# resistance_measuring_board.net
KiCad netlist of a schematic drawn in EAGLE
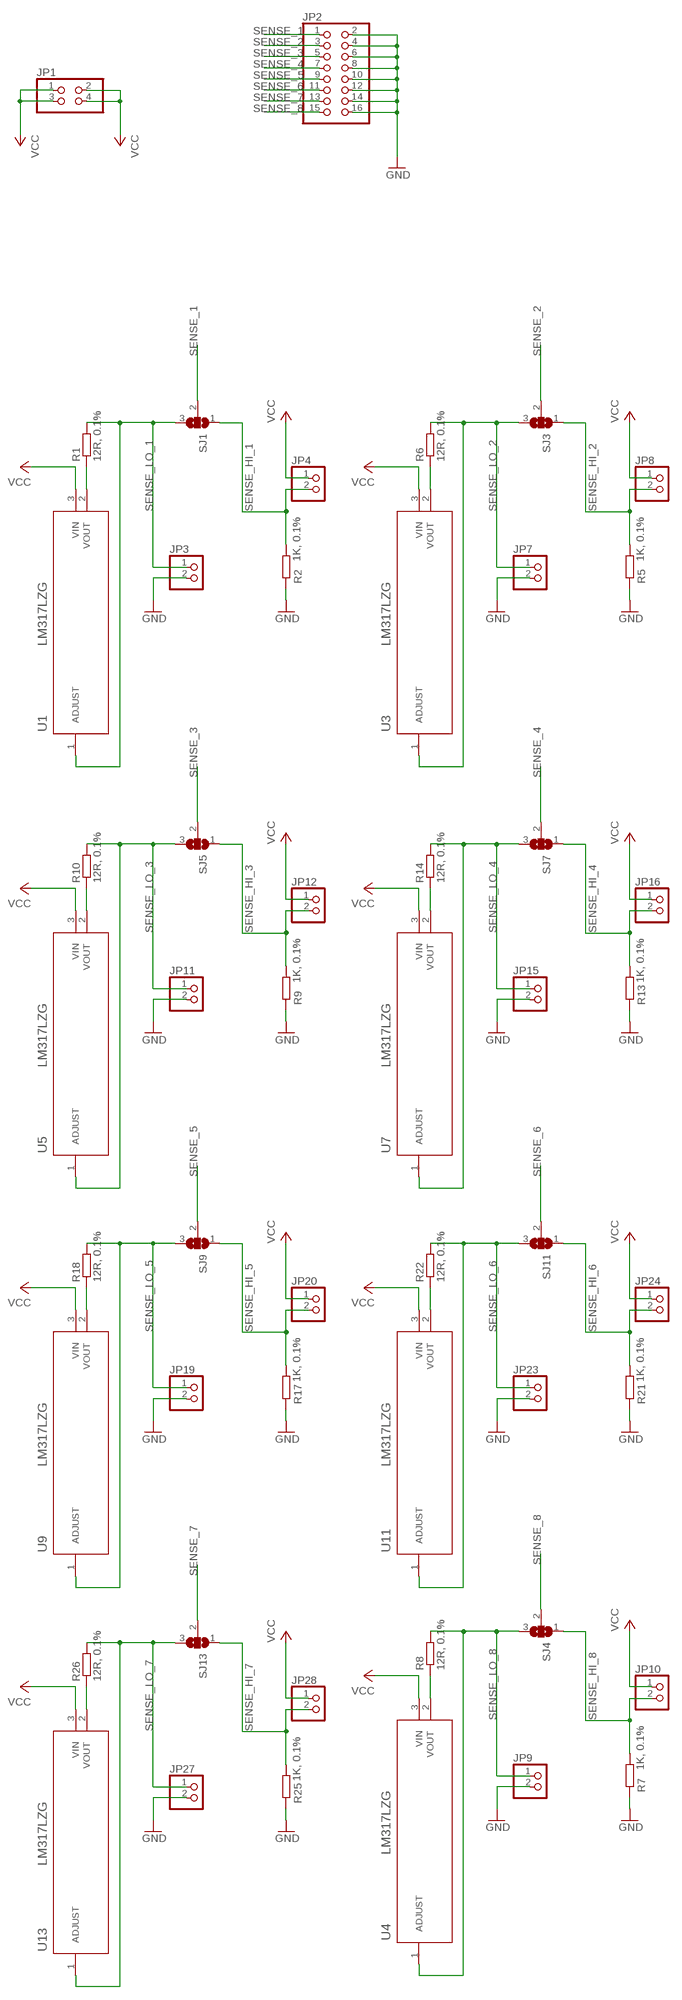
[diagram p0: schematic, sheet 1]

(export (version "E")
  (design (tool "Eeschema 10.0.6"))
  (components
    (comp (ref "JP1")
      (value "PINHD-2X2/90")
      (footprint "eagle-import:2X02_90")
      (libsource (lib "eagle-import") (part "PINHD-2X2/90"))
    )
    (comp (ref "JP2")
      (value "PINHD-2X8/90")
      (footprint "eagle-import:2X08_90")
      (libsource (lib "eagle-import") (part "PINHD-2X8/90"))
    )
    (comp (ref "JP3")
      (value "PINHD-1X2")
      (footprint "eagle-import:1X02")
      (libsource (lib "eagle-import") (part "PINHD-1X2"))
    )
    (comp (ref "JP4")
      (value "PINHD-1X2")
      (footprint "eagle-import:1X02")
      (libsource (lib "eagle-import") (part "PINHD-1X2"))
    )
    (comp (ref "JP7")
      (value "PINHD-1X2")
      (footprint "eagle-import:1X02")
      (libsource (lib "eagle-import") (part "PINHD-1X2"))
    )
    (comp (ref "JP8")
      (value "PINHD-1X2")
      (footprint "eagle-import:1X02")
      (libsource (lib "eagle-import") (part "PINHD-1X2"))
    )
    (comp (ref "JP9")
      (value "PINHD-1X2")
      (footprint "eagle-import:1X02")
      (libsource (lib "eagle-import") (part "PINHD-1X2"))
    )
    (comp (ref "JP10")
      (value "PINHD-1X2")
      (footprint "eagle-import:1X02")
      (libsource (lib "eagle-import") (part "PINHD-1X2"))
    )
    (comp (ref "JP11")
      (value "PINHD-1X2")
      (footprint "eagle-import:1X02")
      (libsource (lib "eagle-import") (part "PINHD-1X2"))
    )
    (comp (ref "JP12")
      (value "PINHD-1X2")
      (footprint "eagle-import:1X02")
      (libsource (lib "eagle-import") (part "PINHD-1X2"))
    )
    (comp (ref "JP15")
      (value "PINHD-1X2")
      (footprint "eagle-import:1X02")
      (libsource (lib "eagle-import") (part "PINHD-1X2"))
    )
    (comp (ref "JP16")
      (value "PINHD-1X2")
      (footprint "eagle-import:1X02")
      (libsource (lib "eagle-import") (part "PINHD-1X2"))
    )
    (comp (ref "JP19")
      (value "PINHD-1X2")
      (footprint "eagle-import:1X02")
      (libsource (lib "eagle-import") (part "PINHD-1X2"))
    )
    (comp (ref "JP20")
      (value "PINHD-1X2")
      (footprint "eagle-import:1X02")
      (libsource (lib "eagle-import") (part "PINHD-1X2"))
    )
    (comp (ref "JP23")
      (value "PINHD-1X2")
      (footprint "eagle-import:1X02")
      (libsource (lib "eagle-import") (part "PINHD-1X2"))
    )
    (comp (ref "JP24")
      (value "PINHD-1X2")
      (footprint "eagle-import:1X02")
      (libsource (lib "eagle-import") (part "PINHD-1X2"))
    )
    (comp (ref "JP27")
      (value "PINHD-1X2")
      (footprint "eagle-import:1X02")
      (libsource (lib "eagle-import") (part "PINHD-1X2"))
    )
    (comp (ref "JP28")
      (value "PINHD-1X2")
      (footprint "eagle-import:1X02")
      (libsource (lib "eagle-import") (part "PINHD-1X2"))
    )
    (comp (ref "R1")
      (value "12R, 0.1%")
      (footprint "eagle-import:R0603")
      (libsource (lib "eagle-import") (part "R-EU_R0603"))
    )
    (comp (ref "R2")
      (value "1K, 0.1%")
      (footprint "eagle-import:R1206")
      (libsource (lib "eagle-import") (part "R-EU_R1206"))
    )
    (comp (ref "R5")
      (value "1K, 0.1%")
      (footprint "eagle-import:R1206")
      (libsource (lib "eagle-import") (part "R-EU_R1206"))
    )
    (comp (ref "R6")
      (value "12R, 0.1%")
      (footprint "eagle-import:R0603")
      (libsource (lib "eagle-import") (part "R-EU_R0603"))
    )
    (comp (ref "R7")
      (value "1K, 0.1%")
      (footprint "eagle-import:R1206")
      (libsource (lib "eagle-import") (part "R-EU_R1206"))
    )
    (comp (ref "R8")
      (value "12R, 0.1%")
      (footprint "eagle-import:R0603")
      (libsource (lib "eagle-import") (part "R-EU_R0603"))
    )
    (comp (ref "R9")
      (value "1K, 0.1%")
      (footprint "eagle-import:R1206")
      (libsource (lib "eagle-import") (part "R-EU_R1206"))
    )
    (comp (ref "R10")
      (value "12R, 0.1%")
      (footprint "eagle-import:R0603")
      (libsource (lib "eagle-import") (part "R-EU_R0603"))
    )
    (comp (ref "R13")
      (value "1K, 0.1%")
      (footprint "eagle-import:R1206")
      (libsource (lib "eagle-import") (part "R-EU_R1206"))
    )
    (comp (ref "R14")
      (value "12R, 0.1%")
      (footprint "eagle-import:R0603")
      (libsource (lib "eagle-import") (part "R-EU_R0603"))
    )
    (comp (ref "R17")
      (value "1K, 0.1%")
      (footprint "eagle-import:R1206")
      (libsource (lib "eagle-import") (part "R-EU_R1206"))
    )
    (comp (ref "R18")
      (value "12R, 0.1%")
      (footprint "eagle-import:R0603")
      (libsource (lib "eagle-import") (part "R-EU_R0603"))
    )
    (comp (ref "R21")
      (value "1K, 0.1%")
      (footprint "eagle-import:R1206")
      (libsource (lib "eagle-import") (part "R-EU_R1206"))
    )
    (comp (ref "R22")
      (value "12R, 0.1%")
      (footprint "eagle-import:R0603")
      (libsource (lib "eagle-import") (part "R-EU_R0603"))
    )
    (comp (ref "R25")
      (value "1K, 0.1%")
      (footprint "eagle-import:R1206")
      (libsource (lib "eagle-import") (part "R-EU_R1206"))
    )
    (comp (ref "R26")
      (value "12R, 0.1%")
      (footprint "eagle-import:R0603")
      (libsource (lib "eagle-import") (part "R-EU_R0603"))
    )
    (comp (ref "SJ1")
      (value "SJ2W")
      (footprint "eagle-import:SJ_2")
      (libsource (lib "eagle-import") (part "SJ2W"))
    )
    (comp (ref "SJ3")
      (value "SJ2W")
      (footprint "eagle-import:SJ_2")
      (libsource (lib "eagle-import") (part "SJ2W"))
    )
    (comp (ref "SJ4")
      (value "SJ2W")
      (footprint "eagle-import:SJ_2")
      (libsource (lib "eagle-import") (part "SJ2W"))
    )
    (comp (ref "SJ5")
      (value "SJ2W")
      (footprint "eagle-import:SJ_2")
      (libsource (lib "eagle-import") (part "SJ2W"))
    )
    (comp (ref "SJ7")
      (value "SJ2W")
      (footprint "eagle-import:SJ_2")
      (libsource (lib "eagle-import") (part "SJ2W"))
    )
    (comp (ref "SJ9")
      (value "SJ2W")
      (footprint "eagle-import:SJ_2")
      (libsource (lib "eagle-import") (part "SJ2W"))
    )
    (comp (ref "SJ11")
      (value "SJ2W")
      (footprint "eagle-import:SJ_2")
      (libsource (lib "eagle-import") (part "SJ2W"))
    )
    (comp (ref "SJ13")
      (value "SJ2W")
      (footprint "eagle-import:SJ_2")
      (libsource (lib "eagle-import") (part "SJ2W"))
    )
    (comp (ref "U1")
      (value "LM317LZG")
      (footprint "eagle-import:TO-92_ONS")
      (libsource (lib "eagle-import") (part "LM317LZG"))
    )
    (comp (ref "U3")
      (value "LM317LZG")
      (footprint "eagle-import:TO-92_ONS")
      (libsource (lib "eagle-import") (part "LM317LZG"))
    )
    (comp (ref "U4")
      (value "LM317LZG")
      (footprint "eagle-import:TO-92_ONS")
      (libsource (lib "eagle-import") (part "LM317LZG"))
    )
    (comp (ref "U5")
      (value "LM317LZG")
      (footprint "eagle-import:TO-92_ONS")
      (libsource (lib "eagle-import") (part "LM317LZG"))
    )
    (comp (ref "U7")
      (value "LM317LZG")
      (footprint "eagle-import:TO-92_ONS")
      (libsource (lib "eagle-import") (part "LM317LZG"))
    )
    (comp (ref "U9")
      (value "LM317LZG")
      (footprint "eagle-import:TO-92_ONS")
      (libsource (lib "eagle-import") (part "LM317LZG"))
    )
    (comp (ref "U11")
      (value "LM317LZG")
      (footprint "eagle-import:TO-92_ONS")
      (libsource (lib "eagle-import") (part "LM317LZG"))
    )
    (comp (ref "U13")
      (value "LM317LZG")
      (footprint "eagle-import:TO-92_ONS")
      (libsource (lib "eagle-import") (part "LM317LZG"))
    )
  )
  (nets
    (net (code "1") (name "/SENSE_1") (class "Default")
      (node (ref "JP2") (pin "1") (pinfunction "1_1") (pintype "passive"))
      (node (ref "SJ1") (pin "2") (pinfunction "2_2") (pintype "passive"))
    )
    (net (code "2") (name "/SENSE_2") (class "Default")
      (node (ref "JP2") (pin "3") (pinfunction "3_3") (pintype "passive"))
      (node (ref "SJ3") (pin "2") (pinfunction "2_2") (pintype "passive"))
    )
    (net (code "3") (name "/SENSE_3") (class "Default")
      (node (ref "JP2") (pin "5") (pinfunction "5_5") (pintype "passive"))
      (node (ref "SJ5") (pin "2") (pinfunction "2_2") (pintype "passive"))
    )
    (net (code "4") (name "/SENSE_4") (class "Default")
      (node (ref "JP2") (pin "7") (pinfunction "7_7") (pintype "passive"))
      (node (ref "SJ7") (pin "2") (pinfunction "2_2") (pintype "passive"))
    )
    (net (code "5") (name "/SENSE_5") (class "Default")
      (node (ref "JP2") (pin "9") (pinfunction "9_9") (pintype "passive"))
      (node (ref "SJ9") (pin "2") (pinfunction "2_2") (pintype "passive"))
    )
    (net (code "6") (name "/SENSE_6") (class "Default")
      (node (ref "JP2") (pin "11") (pinfunction "11_11") (pintype "passive"))
      (node (ref "SJ11") (pin "2") (pinfunction "2_2") (pintype "passive"))
    )
    (net (code "7") (name "/SENSE_7") (class "Default")
      (node (ref "JP2") (pin "13") (pinfunction "13_13") (pintype "passive"))
      (node (ref "SJ13") (pin "2") (pinfunction "2_2") (pintype "passive"))
    )
    (net (code "8") (name "/SENSE_8") (class "Default")
      (node (ref "JP2") (pin "15") (pinfunction "15_15") (pintype "passive"))
      (node (ref "SJ4") (pin "2") (pinfunction "2_2") (pintype "passive"))
    )
    (net (code "9") (name "/SENSE_HI_1") (class "Default")
      (node (ref "JP4") (pin "2") (pinfunction "2_2") (pintype "passive"))
      (node (ref "R2") (pin "2") (pinfunction "2_2") (pintype "passive"))
      (node (ref "SJ1") (pin "1") (pinfunction "1_1") (pintype "passive"))
    )
    (net (code "10") (name "/SENSE_HI_2") (class "Default")
      (node (ref "JP8") (pin "2") (pinfunction "2_2") (pintype "passive"))
      (node (ref "R5") (pin "2") (pinfunction "2_2") (pintype "passive"))
      (node (ref "SJ3") (pin "1") (pinfunction "1_1") (pintype "passive"))
    )
    (net (code "11") (name "/SENSE_HI_3") (class "Default")
      (node (ref "JP12") (pin "2") (pinfunction "2_2") (pintype "passive"))
      (node (ref "R9") (pin "2") (pinfunction "2_2") (pintype "passive"))
      (node (ref "SJ5") (pin "1") (pinfunction "1_1") (pintype "passive"))
    )
    (net (code "12") (name "/SENSE_HI_4") (class "Default")
      (node (ref "JP16") (pin "2") (pinfunction "2_2") (pintype "passive"))
      (node (ref "R13") (pin "2") (pinfunction "2_2") (pintype "passive"))
      (node (ref "SJ7") (pin "1") (pinfunction "1_1") (pintype "passive"))
    )
    (net (code "13") (name "/SENSE_HI_5") (class "Default")
      (node (ref "JP20") (pin "2") (pinfunction "2_2") (pintype "passive"))
      (node (ref "R17") (pin "2") (pinfunction "2_2") (pintype "passive"))
      (node (ref "SJ9") (pin "1") (pinfunction "1_1") (pintype "passive"))
    )
    (net (code "14") (name "/SENSE_HI_6") (class "Default")
      (node (ref "JP24") (pin "2") (pinfunction "2_2") (pintype "passive"))
      (node (ref "R21") (pin "2") (pinfunction "2_2") (pintype "passive"))
      (node (ref "SJ11") (pin "1") (pinfunction "1_1") (pintype "passive"))
    )
    (net (code "15") (name "/SENSE_HI_7") (class "Default")
      (node (ref "JP28") (pin "2") (pinfunction "2_2") (pintype "passive"))
      (node (ref "R25") (pin "2") (pinfunction "2_2") (pintype "passive"))
      (node (ref "SJ13") (pin "1") (pinfunction "1_1") (pintype "passive"))
    )
    (net (code "16") (name "/SENSE_HI_8") (class "Default")
      (node (ref "JP10") (pin "2") (pinfunction "2_2") (pintype "passive"))
      (node (ref "R7") (pin "2") (pinfunction "2_2") (pintype "passive"))
      (node (ref "SJ4") (pin "1") (pinfunction "1_1") (pintype "passive"))
    )
    (net (code "17") (name "/SENSE_LO_1") (class "Default")
      (node (ref "JP3") (pin "1") (pinfunction "1_1") (pintype "passive"))
      (node (ref "R1") (pin "2") (pinfunction "2_2") (pintype "passive"))
      (node (ref "SJ1") (pin "3") (pinfunction "3_3") (pintype "passive"))
      (node (ref "U1") (pin "1") (pinfunction "ADJUST_1") (pintype "passive"))
    )
    (net (code "18") (name "/SENSE_LO_2") (class "Default")
      (node (ref "JP7") (pin "1") (pinfunction "1_1") (pintype "passive"))
      (node (ref "R6") (pin "2") (pinfunction "2_2") (pintype "passive"))
      (node (ref "SJ3") (pin "3") (pinfunction "3_3") (pintype "passive"))
      (node (ref "U3") (pin "1") (pinfunction "ADJUST_1") (pintype "passive"))
    )
    (net (code "19") (name "/SENSE_LO_3") (class "Default")
      (node (ref "JP11") (pin "1") (pinfunction "1_1") (pintype "passive"))
      (node (ref "R10") (pin "2") (pinfunction "2_2") (pintype "passive"))
      (node (ref "SJ5") (pin "3") (pinfunction "3_3") (pintype "passive"))
      (node (ref "U5") (pin "1") (pinfunction "ADJUST_1") (pintype "passive"))
    )
    (net (code "20") (name "/SENSE_LO_4") (class "Default")
      (node (ref "JP15") (pin "1") (pinfunction "1_1") (pintype "passive"))
      (node (ref "R14") (pin "2") (pinfunction "2_2") (pintype "passive"))
      (node (ref "SJ7") (pin "3") (pinfunction "3_3") (pintype "passive"))
      (node (ref "U7") (pin "1") (pinfunction "ADJUST_1") (pintype "passive"))
    )
    (net (code "21") (name "/SENSE_LO_5") (class "Default")
      (node (ref "JP19") (pin "1") (pinfunction "1_1") (pintype "passive"))
      (node (ref "R18") (pin "2") (pinfunction "2_2") (pintype "passive"))
      (node (ref "SJ9") (pin "3") (pinfunction "3_3") (pintype "passive"))
      (node (ref "U9") (pin "1") (pinfunction "ADJUST_1") (pintype "passive"))
    )
    (net (code "22") (name "/SENSE_LO_6") (class "Default")
      (node (ref "JP23") (pin "1") (pinfunction "1_1") (pintype "passive"))
      (node (ref "R22") (pin "2") (pinfunction "2_2") (pintype "passive"))
      (node (ref "SJ11") (pin "3") (pinfunction "3_3") (pintype "passive"))
      (node (ref "U11") (pin "1") (pinfunction "ADJUST_1") (pintype "passive"))
    )
    (net (code "23") (name "/SENSE_LO_7") (class "Default")
      (node (ref "JP27") (pin "1") (pinfunction "1_1") (pintype "passive"))
      (node (ref "R26") (pin "2") (pinfunction "2_2") (pintype "passive"))
      (node (ref "SJ13") (pin "3") (pinfunction "3_3") (pintype "passive"))
      (node (ref "U13") (pin "1") (pinfunction "ADJUST_1") (pintype "passive"))
    )
    (net (code "24") (name "/SENSE_LO_8") (class "Default")
      (node (ref "JP9") (pin "1") (pinfunction "1_1") (pintype "passive"))
      (node (ref "R8") (pin "2") (pinfunction "2_2") (pintype "passive"))
      (node (ref "SJ4") (pin "3") (pinfunction "3_3") (pintype "passive"))
      (node (ref "U4") (pin "1") (pinfunction "ADJUST_1") (pintype "passive"))
    )
    (net (code "25") (name "GND") (class "Default")
      (node (ref "JP11") (pin "2") (pinfunction "2_2") (pintype "passive"))
      (node (ref "JP15") (pin "2") (pinfunction "2_2") (pintype "passive"))
      (node (ref "JP19") (pin "2") (pinfunction "2_2") (pintype "passive"))
      (node (ref "JP2") (pin "10") (pinfunction "10_10") (pintype "passive"))
      (node (ref "JP2") (pin "12") (pinfunction "12_12") (pintype "passive"))
      (node (ref "JP2") (pin "14") (pinfunction "14_14") (pintype "passive"))
      (node (ref "JP2") (pin "16") (pinfunction "16_16") (pintype "passive"))
      (node (ref "JP2") (pin "2") (pinfunction "2_2") (pintype "passive"))
      (node (ref "JP2") (pin "4") (pinfunction "4_4") (pintype "passive"))
      (node (ref "JP2") (pin "6") (pinfunction "6_6") (pintype "passive"))
      (node (ref "JP2") (pin "8") (pinfunction "8_8") (pintype "passive"))
      (node (ref "JP23") (pin "2") (pinfunction "2_2") (pintype "passive"))
      (node (ref "JP27") (pin "2") (pinfunction "2_2") (pintype "passive"))
      (node (ref "JP3") (pin "2") (pinfunction "2_2") (pintype "passive"))
      (node (ref "JP7") (pin "2") (pinfunction "2_2") (pintype "passive"))
      (node (ref "JP9") (pin "2") (pinfunction "2_2") (pintype "passive"))
      (node (ref "R13") (pin "1") (pinfunction "1_1") (pintype "passive"))
      (node (ref "R17") (pin "1") (pinfunction "1_1") (pintype "passive"))
      (node (ref "R2") (pin "1") (pinfunction "1_1") (pintype "passive"))
      (node (ref "R21") (pin "1") (pinfunction "1_1") (pintype "passive"))
      (node (ref "R25") (pin "1") (pinfunction "1_1") (pintype "passive"))
      (node (ref "R5") (pin "1") (pinfunction "1_1") (pintype "passive"))
      (node (ref "R7") (pin "1") (pinfunction "1_1") (pintype "passive"))
      (node (ref "R9") (pin "1") (pinfunction "1_1") (pintype "passive"))
    )
    (net (code "26") (name "Net-(U1-VOUT)") (class "Default")
      (node (ref "R1") (pin "1") (pinfunction "1_1") (pintype "passive"))
      (node (ref "U1") (pin "2") (pinfunction "VOUT_2") (pintype "output"))
    )
    (net (code "27") (name "Net-(U3-VOUT)") (class "Default")
      (node (ref "R6") (pin "1") (pinfunction "1_1") (pintype "passive"))
      (node (ref "U3") (pin "2") (pinfunction "VOUT_2") (pintype "output"))
    )
    (net (code "28") (name "Net-(U4-VOUT)") (class "Default")
      (node (ref "R8") (pin "1") (pinfunction "1_1") (pintype "passive"))
      (node (ref "U4") (pin "2") (pinfunction "VOUT_2") (pintype "output"))
    )
    (net (code "29") (name "Net-(U5-VOUT)") (class "Default")
      (node (ref "R10") (pin "1") (pinfunction "1_1") (pintype "passive"))
      (node (ref "U5") (pin "2") (pinfunction "VOUT_2") (pintype "output"))
    )
    (net (code "30") (name "Net-(U7-VOUT)") (class "Default")
      (node (ref "R14") (pin "1") (pinfunction "1_1") (pintype "passive"))
      (node (ref "U7") (pin "2") (pinfunction "VOUT_2") (pintype "output"))
    )
    (net (code "31") (name "Net-(U9-VOUT)") (class "Default")
      (node (ref "R18") (pin "1") (pinfunction "1_1") (pintype "passive"))
      (node (ref "U9") (pin "2") (pinfunction "VOUT_2") (pintype "output"))
    )
    (net (code "32") (name "Net-(U11-VOUT)") (class "Default")
      (node (ref "R22") (pin "1") (pinfunction "1_1") (pintype "passive"))
      (node (ref "U11") (pin "2") (pinfunction "VOUT_2") (pintype "output"))
    )
    (net (code "33") (name "Net-(U13-VOUT)") (class "Default")
      (node (ref "R26") (pin "1") (pinfunction "1_1") (pintype "passive"))
      (node (ref "U13") (pin "2") (pinfunction "VOUT_2") (pintype "output"))
    )
    (net (code "34") (name "VCC") (class "Default")
      (node (ref "JP1") (pin "1") (pinfunction "1_1") (pintype "passive"))
      (node (ref "JP1") (pin "2") (pinfunction "2_2") (pintype "passive"))
      (node (ref "JP1") (pin "3") (pinfunction "3_3") (pintype "passive"))
      (node (ref "JP1") (pin "4") (pinfunction "4_4") (pintype "passive"))
      (node (ref "JP10") (pin "1") (pinfunction "1_1") (pintype "passive"))
      (node (ref "JP12") (pin "1") (pinfunction "1_1") (pintype "passive"))
      (node (ref "JP16") (pin "1") (pinfunction "1_1") (pintype "passive"))
      (node (ref "JP20") (pin "1") (pinfunction "1_1") (pintype "passive"))
      (node (ref "JP24") (pin "1") (pinfunction "1_1") (pintype "passive"))
      (node (ref "JP28") (pin "1") (pinfunction "1_1") (pintype "passive"))
      (node (ref "JP4") (pin "1") (pinfunction "1_1") (pintype "passive"))
      (node (ref "JP8") (pin "1") (pinfunction "1_1") (pintype "passive"))
      (node (ref "U1") (pin "3") (pinfunction "VIN_3") (pintype "input"))
      (node (ref "U11") (pin "3") (pinfunction "VIN_3") (pintype "input"))
      (node (ref "U13") (pin "3") (pinfunction "VIN_3") (pintype "input"))
      (node (ref "U3") (pin "3") (pinfunction "VIN_3") (pintype "input"))
      (node (ref "U4") (pin "3") (pinfunction "VIN_3") (pintype "input"))
      (node (ref "U5") (pin "3") (pinfunction "VIN_3") (pintype "input"))
      (node (ref "U7") (pin "3") (pinfunction "VIN_3") (pintype "input"))
      (node (ref "U9") (pin "3") (pinfunction "VIN_3") (pintype "input"))
    )
  )
)
